# Frontend.net
KiCad netlist of a schematic drawn in Altium Designer
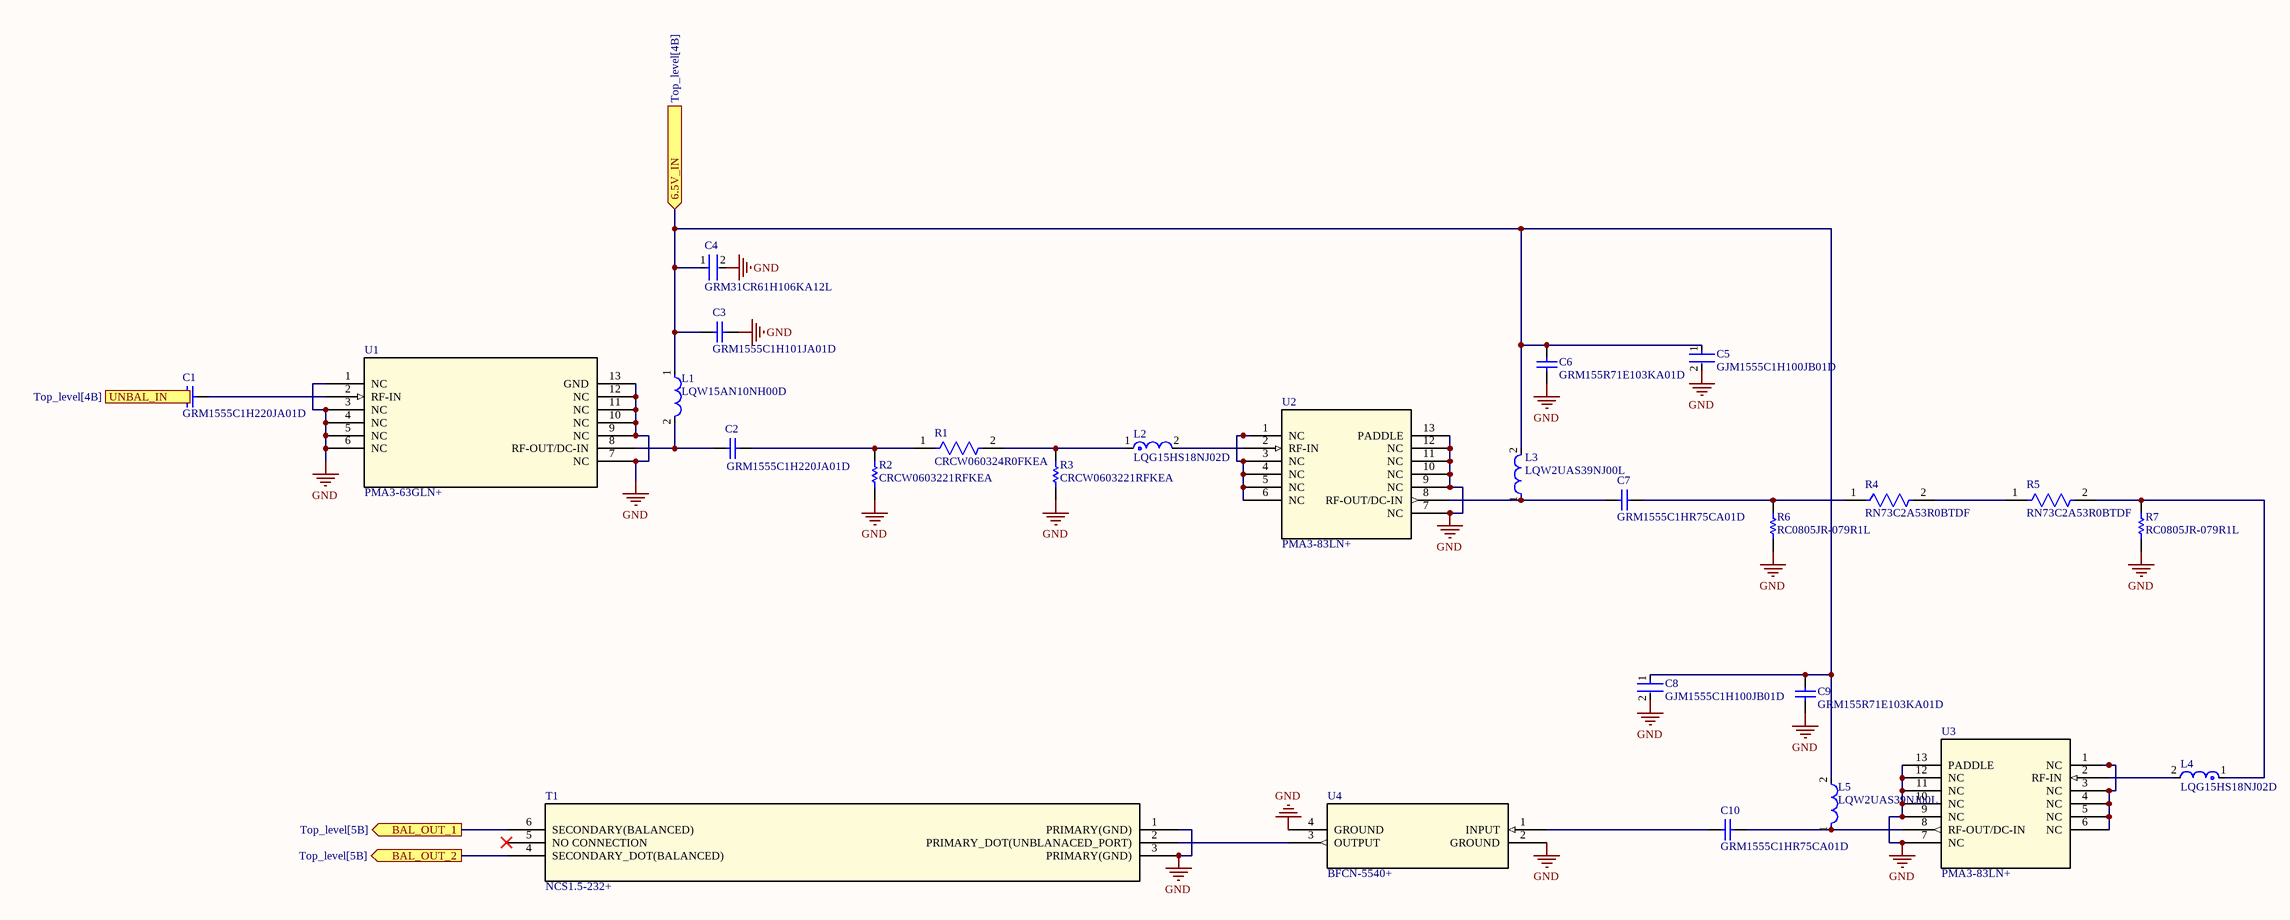
[diagram p0: Frontend.SchDoc]

(export (version "E")
  (design (tool "Eeschema 10.0.6"))
  (components
    (comp (ref "C1")
      (value "GRM1555C1H220JA01D")
      (footprint "CAPC1005X55X25NL05T10")
      (fields (field (name "MANUFACTURER") "Murata"))
      (libsource (lib "Altium Content Vault") (part "CAP"))
    )
    (comp (ref "C2")
      (value "GRM1555C1H220JA01D")
      (footprint "CAPC1005X55X25NL05T10")
      (fields (field (name "MANUFACTURER") "Murata"))
      (libsource (lib "Altium Content Vault") (part "CAP"))
    )
    (comp (ref "C3")
      (value "GRM1555C1H101JA01D")
      (footprint "CAPC1005X55X25ML05T10")
      (fields (field (name "MANUFACTURER") "Murata"))
      (libsource (lib "Altium Content Vault") (part "CAP"))
    )
    (comp (ref "C4")
      (value "GRM31CR61H106KA12L")
      (footprint "FP-GRM31-0_2-MFG")
      (description "CAP CER 10UF 50V X5R 1206")
      (fields
        (field (name "OCTOPART") "https://octopart.com/grm31cr61h106ka12l-murata-18903335")
        (field (name "TOLERANCE") "10%")
      )
      (libsource (lib "Altium Content Vault") (part "11868f565c42a9108669ba33697ecf6"))
    )
    (comp (ref "C5")
      (value "GJM1555C1H100JB01D")
      (footprint "FP-GJM155-0_05-IPC_A")
      (description "Multi-Layer Ceramic Capacitor 10pF C0G  ±5% 0402 Paper T/R")
      (fields (field (name "TOLERANCE") "5%") (field (name "VOLTAGE") "50V"))
      (libsource (lib "Altium Content Vault") (part "02cd4be3c70576c341d710602a673aa"))
    )
    (comp (ref "C6")
      (value "GRM155R71E103KA01D")
      (footprint "CAPC1005X55X25LL05T10")
      (fields (field (name "MANUFACTURER") "Murata"))
      (libsource (lib "Altium Content Vault") (part "CAP"))
    )
    (comp (ref "C7")
      (value "GRM1555C1HR75CA01D")
      (footprint "CAPC1005X55X25LL05T10")
      (fields (field (name "MANUFACTURER") "Murata"))
      (libsource (lib "Altium Content Vault") (part "CAP"))
    )
    (comp (ref "C8")
      (value "GJM1555C1H100JB01D")
      (footprint "FP-GJM155-0_05-IPC_A")
      (description "Multi-Layer Ceramic Capacitor 10pF C0G  ±5% 0402 Paper T/R")
      (fields (field (name "TOLERANCE") "5%") (field (name "VOLTAGE") "50V"))
      (libsource (lib "Altium Content Vault") (part "02cd4be3c70576c341d710602a673aa"))
    )
    (comp (ref "C9")
      (value "GRM155R71E103KA01D")
      (footprint "CAPC1005X55X25LL05T10")
      (fields (field (name "MANUFACTURER") "Murata"))
      (libsource (lib "Altium Content Vault") (part "CAP"))
    )
    (comp (ref "C10")
      (value "GRM1555C1HR75CA01D")
      (footprint "CAPC1005X55X25LL05T10")
      (fields (field (name "MANUFACTURER") "Murata"))
      (libsource (lib "Altium Content Vault") (part "CAP"))
    )
    (comp (ref "L1")
      (value "LQW15AN10NH00D")
      (footprint "FP-LQW15AN_00-W0_6-0_1-MFG")
      (description "Wire Wound RF Inductor 10nH ±3% 500mA 0.17Ω 0402 (1005)")
      (fields (field (name "TOLERANCE") "3%"))
      (libsource (lib "Altium Content Vault") (part "725321dda6339637d4d059423bc1c3c"))
    )
    (comp (ref "L2")
      (value "LQG15HS18NJ02D")
      (footprint "FP-LQG15HH_02-MFG")
      (description "Multilayer type RF Inductor 18nH ±5% 0.36Ω 400mA 0402")
      (fields (field (name "TOLERANCE") "5%"))
      (libsource (lib "Altium Content Vault") (part "4cc4b267dca4c8e51f7102f422741d8"))
    )
    (comp (ref "L3")
      (value "LQW2UAS39NJ00L")
      (footprint "FP-LQW2UAS_00-MFG")
      (description "Wire Wound RF Inductor 39nH ±5% 1000mA 0.15Ω 1008 (2520)")
      (fields (field (name "TOLERANCE") "5%"))
      (libsource (lib "Altium Content Vault") (part "725321dda6339637d4d059423bc1c3c"))
    )
    (comp (ref "L4")
      (value "LQG15HS18NJ02D")
      (footprint "FP-LQG15HH_02-MFG")
      (description "Multilayer type RF Inductor 18nH ±5% 0.36Ω 400mA 0402")
      (fields (field (name "TOLERANCE") "5%"))
      (libsource (lib "") (part "4cc4b267dca4c8e51f7102f422741d8_1"))
    )
    (comp (ref "L5")
      (value "LQW2UAS39NJ00L")
      (footprint "FP-LQW2UAS_00-MFG")
      (description "Wire Wound RF Inductor 39nH ±5% 1000mA 0.15Ω 1008 (2520)")
      (fields (field (name "TOLERANCE") "5%"))
      (libsource (lib "") (part "725321dda6339637d4d059423bc1c3c_1"))
    )
    (comp (ref "R1")
      (value "CRCW060324R0FKEA")
      (footprint "FP-CRCW0603-e3-MFG")
      (description "RES Thick Film, 24Ω, 1%, 0.1W, 100ppm/°C, 0603")
      (fields (field (name "TOLERANCE") "1%"))
      (libsource (lib "Altium Content Vault") (part "1029c3af85768c4190bb7ad29bc67b5"))
    )
    (comp (ref "R2")
      (value "CRCW0603221RFKEA")
      (footprint "RESC1609X50X30LL10T20")
      (fields (field (name "MANUFACTURER") "Vishay Dale"))
      (libsource (lib "Altium Content Vault") (part "RES"))
    )
    (comp (ref "R3")
      (value "CRCW0603221RFKEA")
      (footprint "RESC1609X50X30LL10T20")
      (fields (field (name "MANUFACTURER") "Vishay Dale"))
      (libsource (lib "Altium Content Vault") (part "RES"))
    )
    (comp (ref "R4")
      (value "RN73C2A53R0BTDF")
      (footprint "FP-RN732A-MFG")
      (description "SMD Chip Resistor, Thin Film, 53.0Ω, 100 V, 0805 [2012 Metric], 100 mW, 0.1%, RN73 Series")
      (fields
        (field (name "OCTOPART") "https://octopart.com/rn73c2a53r0btdf-te+connectivity-22742106")
        (field (name "MANUFACTURER") "TE Connectivity")
      )
      (libsource (lib "Altium Content Vault") (part "1029c3af85768c4190bb7ad29bc67b5"))
    )
    (comp (ref "R5")
      (value "RN73C2A53R0BTDF")
      (footprint "FP-RN732A-MFG")
      (description "SMD Chip Resistor, Thin Film, 53.0Ω, 100 V, 0805 [2012 Metric], 100 mW, 0.1%, RN73 Series")
      (fields
        (field (name "OCTOPART") "https://octopart.com/rn73c2a53r0btdf-te+connectivity-22742106")
        (field (name "MANUFACTURER") "TE Connectivity")
      )
      (libsource (lib "Altium Content Vault") (part "1029c3af85768c4190bb7ad29bc67b5"))
    )
    (comp (ref "R6")
      (value "RC0805JR-079R1L")
      (footprint "RESC2013X60X35LL10T20")
      (fields (field (name "MANUFACTURER") "Yageo"))
      (libsource (lib "Altium Content Vault") (part "RES"))
    )
    (comp (ref "R7")
      (value "RC0805JR-079R1L")
      (footprint "RESC2013X60X35LL10T20")
      (fields (field (name "MANUFACTURER") "Yageo"))
      (libsource (lib "Altium Content Vault") (part "RES"))
    )
    (comp (ref "T1")
      (value "NCS1.5-232+")
      (footprint "GE0805C-9_MNC")
      (description "No Description Available")
      (fields (field (name "COPYRIGHT") "Copyright (C) 2023 Ultra Librarian. All rights reserved."))
      (libsource (lib "NCS1P5-232&plus_") (part "NCS1.5-232+"))
    )
    (comp (ref "U1")
      (value "PMA3-63GLN+")
      (footprint "DQ1225_MNC")
      (description "No Description Available")
      (fields (field (name "COPYRIGHT") "Copyright (C) 2023 Ultra Librarian. All rights reserved."))
      (libsource (lib "PMA3-63GLN&plus_") (part "PMA3-63GLN+"))
    )
    (comp (ref "U2")
      (value "PMA3-83LN+")
      (footprint "DQ1225_MNC")
      (description "No Description Available")
      (fields (field (name "COPYRIGHT") "Copyright (C) 2023 Ultra Librarian. All rights reserved."))
      (libsource (lib "") (part "PMA3-83LN+_1"))
    )
    (comp (ref "U3")
      (value "PMA3-83LN+")
      (footprint "DQ1225_MNC")
      (description "No Description Available")
      (fields (field (name "COPYRIGHT") "Copyright (C) 2023 Ultra Librarian. All rights reserved."))
      (libsource (lib "PMA3-83LN&plus_") (part "PMA3-83LN+"))
    )
    (comp (ref "U4")
      (value "BFCN-5540+")
      (footprint "FV1206-4_MNC")
      (description "No Description Available")
      (fields (field (name "COPYRIGHT") "Copyright (C) 2023 Ultra Librarian. All rights reserved."))
      (libsource (lib "BFCN-5540&plus_") (part "BFCN-5540+"))
    )
  )
  (nets
    (net (code "1") (name "/6.5V_IN") (class "Default")
      (node (ref "C3") (pin "1") (pinfunction "1_1") (pintype "passive"))
      (node (ref "C4") (pin "1") (pinfunction "1_1") (pintype "passive"))
      (node (ref "C5") (pin "1") (pinfunction "1_1") (pintype "passive"))
      (node (ref "C6") (pin "2") (pinfunction "2_2") (pintype "passive"))
      (node (ref "C8") (pin "1") (pinfunction "1_1") (pintype "passive"))
      (node (ref "C9") (pin "2") (pinfunction "2_2") (pintype "passive"))
      (node (ref "L1") (pin "1") (pinfunction "1_1") (pintype "passive"))
      (node (ref "L3") (pin "2") (pinfunction "2_2") (pintype "passive"))
      (node (ref "L5") (pin "2") (pinfunction "2_2") (pintype "passive"))
    )
    (net (code "2") (name "/BAL_OUT_1") (class "Default")
      (node (ref "T1") (pin "6") (pinfunction "SECONDARY(BALANCED)_6") (pintype "passive"))
    )
    (net (code "3") (name "/BAL_OUT_2") (class "Default")
      (node (ref "T1") (pin "4") (pinfunction "SECONDARY_DOT(BALANCED)_4") (pintype "passive"))
    )
    (net (code "5") (name "GND") (class "Default")
      (node (ref "C3") (pin "2") (pinfunction "2_2") (pintype "passive"))
      (node (ref "C4") (pin "2") (pinfunction "2_2") (pintype "passive"))
      (node (ref "C5") (pin "2") (pinfunction "2_2") (pintype "passive"))
      (node (ref "C6") (pin "1") (pinfunction "1_1") (pintype "passive"))
      (node (ref "C8") (pin "2") (pinfunction "2_2") (pintype "passive"))
      (node (ref "C9") (pin "1") (pinfunction "1_1") (pintype "passive"))
      (node (ref "R2") (pin "1") (pinfunction "1_1") (pintype "passive"))
      (node (ref "R3") (pin "1") (pinfunction "1_1") (pintype "passive"))
      (node (ref "R6") (pin "1") (pinfunction "1_1") (pintype "passive"))
      (node (ref "R7") (pin "1") (pinfunction "1_1") (pintype "passive"))
      (node (ref "T1") (pin "1") (pinfunction "PRIMARY(GND)_1") (pintype "passive"))
      (node (ref "T1") (pin "3") (pinfunction "PRIMARY(GND)_3") (pintype "passive"))
      (node (ref "U1") (pin "1") (pinfunction "NC_1") (pintype "passive"))
      (node (ref "U1") (pin "10") (pinfunction "NC_10") (pintype "passive"))
      (node (ref "U1") (pin "11") (pinfunction "NC_11") (pintype "passive"))
      (node (ref "U1") (pin "12") (pinfunction "NC_12") (pintype "passive"))
      (node (ref "U1") (pin "13") (pinfunction "GND_13") (pintype "power_in"))
      (node (ref "U1") (pin "3") (pinfunction "NC_3") (pintype "passive"))
      (node (ref "U1") (pin "4") (pinfunction "NC_4") (pintype "passive"))
      (node (ref "U1") (pin "5") (pinfunction "NC_5") (pintype "passive"))
      (node (ref "U1") (pin "6") (pinfunction "NC_6") (pintype "passive"))
      (node (ref "U1") (pin "7") (pinfunction "NC_7") (pintype "passive"))
      (node (ref "U1") (pin "9") (pinfunction "NC_9") (pintype "passive"))
      (node (ref "U2") (pin "10") (pinfunction "NC_10") (pintype "passive"))
      (node (ref "U2") (pin "11") (pinfunction "NC_11") (pintype "passive"))
      (node (ref "U2") (pin "12") (pinfunction "NC_12") (pintype "passive"))
      (node (ref "U2") (pin "13") (pinfunction "PADDLE_13") (pintype "power_in"))
      (node (ref "U2") (pin "7") (pinfunction "NC_7") (pintype "passive"))
      (node (ref "U2") (pin "9") (pinfunction "NC_9") (pintype "passive"))
      (node (ref "U3") (pin "10") (pinfunction "NC_10") (pintype "passive"))
      (node (ref "U3") (pin "11") (pinfunction "NC_11") (pintype "passive"))
      (node (ref "U3") (pin "12") (pinfunction "NC_12") (pintype "passive"))
      (node (ref "U3") (pin "13") (pinfunction "PADDLE_13") (pintype "power_in"))
      (node (ref "U3") (pin "7") (pinfunction "NC_7") (pintype "passive"))
      (node (ref "U3") (pin "9") (pinfunction "NC_9") (pintype "passive"))
      (node (ref "U4") (pin "2") (pinfunction "GROUND_2") (pintype "power_in"))
      (node (ref "U4") (pin "4") (pinfunction "GROUND_4") (pintype "power_in"))
    )
    (net (code "6") (name "Net-(C2-Pad2)") (class "Default")
      (node (ref "C2") (pin "2") (pinfunction "2_2") (pintype "passive"))
      (node (ref "R1") (pin "1") (pinfunction "1_1") (pintype "passive"))
      (node (ref "R2") (pin "2") (pinfunction "2_2") (pintype "passive"))
    )
    (net (code "7") (name "Net-(C7-Pad2)") (class "Default")
      (node (ref "C7") (pin "2") (pinfunction "2_2") (pintype "passive"))
      (node (ref "R4") (pin "1") (pinfunction "1_1") (pintype "passive"))
      (node (ref "R6") (pin "2") (pinfunction "2_2") (pintype "passive"))
    )
    (net (code "8") (name "Net-(L2-Pad1)") (class "Default")
      (node (ref "L2") (pin "1") (pinfunction "1_1") (pintype "passive"))
      (node (ref "R1") (pin "2") (pinfunction "2_2") (pintype "passive"))
      (node (ref "R3") (pin "2") (pinfunction "2_2") (pintype "passive"))
    )
    (net (code "9") (name "Net-(L4-Pad1)") (class "Default")
      (node (ref "L4") (pin "1") (pinfunction "1_1") (pintype "passive"))
      (node (ref "R5") (pin "2") (pinfunction "2_2") (pintype "passive"))
      (node (ref "R7") (pin "2") (pinfunction "2_2") (pintype "passive"))
    )
    (net (code "10") (name "Net-(R4-Pad2)") (class "Default")
      (node (ref "R4") (pin "2") (pinfunction "2_2") (pintype "passive"))
      (node (ref "R5") (pin "1") (pinfunction "1_1") (pintype "passive"))
    )
    (net (code "11") (name "Net-(T1-PRIMARY_DOT(UNBLANACED_PORT))") (class "Default")
      (node (ref "T1") (pin "2") (pinfunction "PRIMARY_DOT(UNBLANACED_PORT)_2") (pintype "passive"))
      (node (ref "U4") (pin "3") (pinfunction "OUTPUT_3") (pintype "output"))
    )
    (net (code "12") (name "Net-(U1-RF-IN)") (class "Default")
      (node (ref "C1") (pin "1") (pinfunction "1_1") (pintype "passive"))
      (node (ref "U1") (pin "2") (pinfunction "RF-IN_2") (pintype "input"))
    )
    (net (code "13") (name "Net-(U1-RF-OUT{slash}DC-IN)") (class "Default")
      (node (ref "C2") (pin "1") (pinfunction "1_1") (pintype "passive"))
      (node (ref "L1") (pin "2") (pinfunction "2_2") (pintype "passive"))
      (node (ref "U1") (pin "8") (pinfunction "RF-OUT/DC-IN_8") (pintype "passive"))
    )
    (net (code "14") (name "Net-(U2-NC-Pad1)") (class "Default")
      (node (ref "U2") (pin "1") (pinfunction "NC_1") (pintype "passive"))
      (node (ref "U2") (pin "3") (pinfunction "NC_3") (pintype "passive"))
      (node (ref "U2") (pin "4") (pinfunction "NC_4") (pintype "passive"))
      (node (ref "U2") (pin "5") (pinfunction "NC_5") (pintype "passive"))
      (node (ref "U2") (pin "6") (pinfunction "NC_6") (pintype "passive"))
    )
    (net (code "15") (name "Net-(U2-RF-IN)") (class "Default")
      (node (ref "L2") (pin "2") (pinfunction "2_2") (pintype "passive"))
      (node (ref "U2") (pin "2") (pinfunction "RF-IN_2") (pintype "input"))
    )
    (net (code "16") (name "Net-(U2-RF-OUT{slash}DC-IN)") (class "Default")
      (node (ref "C7") (pin "1") (pinfunction "1_1") (pintype "passive"))
      (node (ref "L3") (pin "1") (pinfunction "1_1") (pintype "passive"))
      (node (ref "U2") (pin "8") (pinfunction "RF-OUT/DC-IN_8") (pintype "output"))
    )
    (net (code "17") (name "Net-(U3-NC-Pad1)") (class "Default")
      (node (ref "U3") (pin "1") (pinfunction "NC_1") (pintype "passive"))
      (node (ref "U3") (pin "3") (pinfunction "NC_3") (pintype "passive"))
      (node (ref "U3") (pin "4") (pinfunction "NC_4") (pintype "passive"))
      (node (ref "U3") (pin "5") (pinfunction "NC_5") (pintype "passive"))
      (node (ref "U3") (pin "6") (pinfunction "NC_6") (pintype "passive"))
    )
    (net (code "18") (name "Net-(U3-RF-IN)") (class "Default")
      (node (ref "L4") (pin "2") (pinfunction "2_2") (pintype "passive"))
      (node (ref "U3") (pin "2") (pinfunction "RF-IN_2") (pintype "input"))
    )
    (net (code "19") (name "Net-(U3-RF-OUT{slash}DC-IN)") (class "Default")
      (node (ref "C10") (pin "1") (pinfunction "1_1") (pintype "passive"))
      (node (ref "L5") (pin "1") (pinfunction "1_1") (pintype "passive"))
      (node (ref "U3") (pin "8") (pinfunction "RF-OUT/DC-IN_8") (pintype "output"))
    )
    (net (code "20") (name "Net-(U4-INPUT)") (class "Default")
      (node (ref "C10") (pin "2") (pinfunction "2_2") (pintype "passive"))
      (node (ref "U4") (pin "1") (pinfunction "INPUT_1") (pintype "input"))
    )
    (net (code "21") (name "unconnected-(C1-Pad2)") (class "Default")
      (node (ref "C1") (pin "2") (pinfunction "2_2") (pintype "passive"))
    )
    (net (code "22") (name "unconnected-(T1-NO_CONNECTION-Pad5)") (class "Default")
      (node (ref "T1") (pin "5") (pinfunction "NO_CONNECTION_5") (pintype "passive+no_connect"))
    )
  )
)
